# SensorBoard.net
KiCad netlist of a schematic drawn in Altium Designer
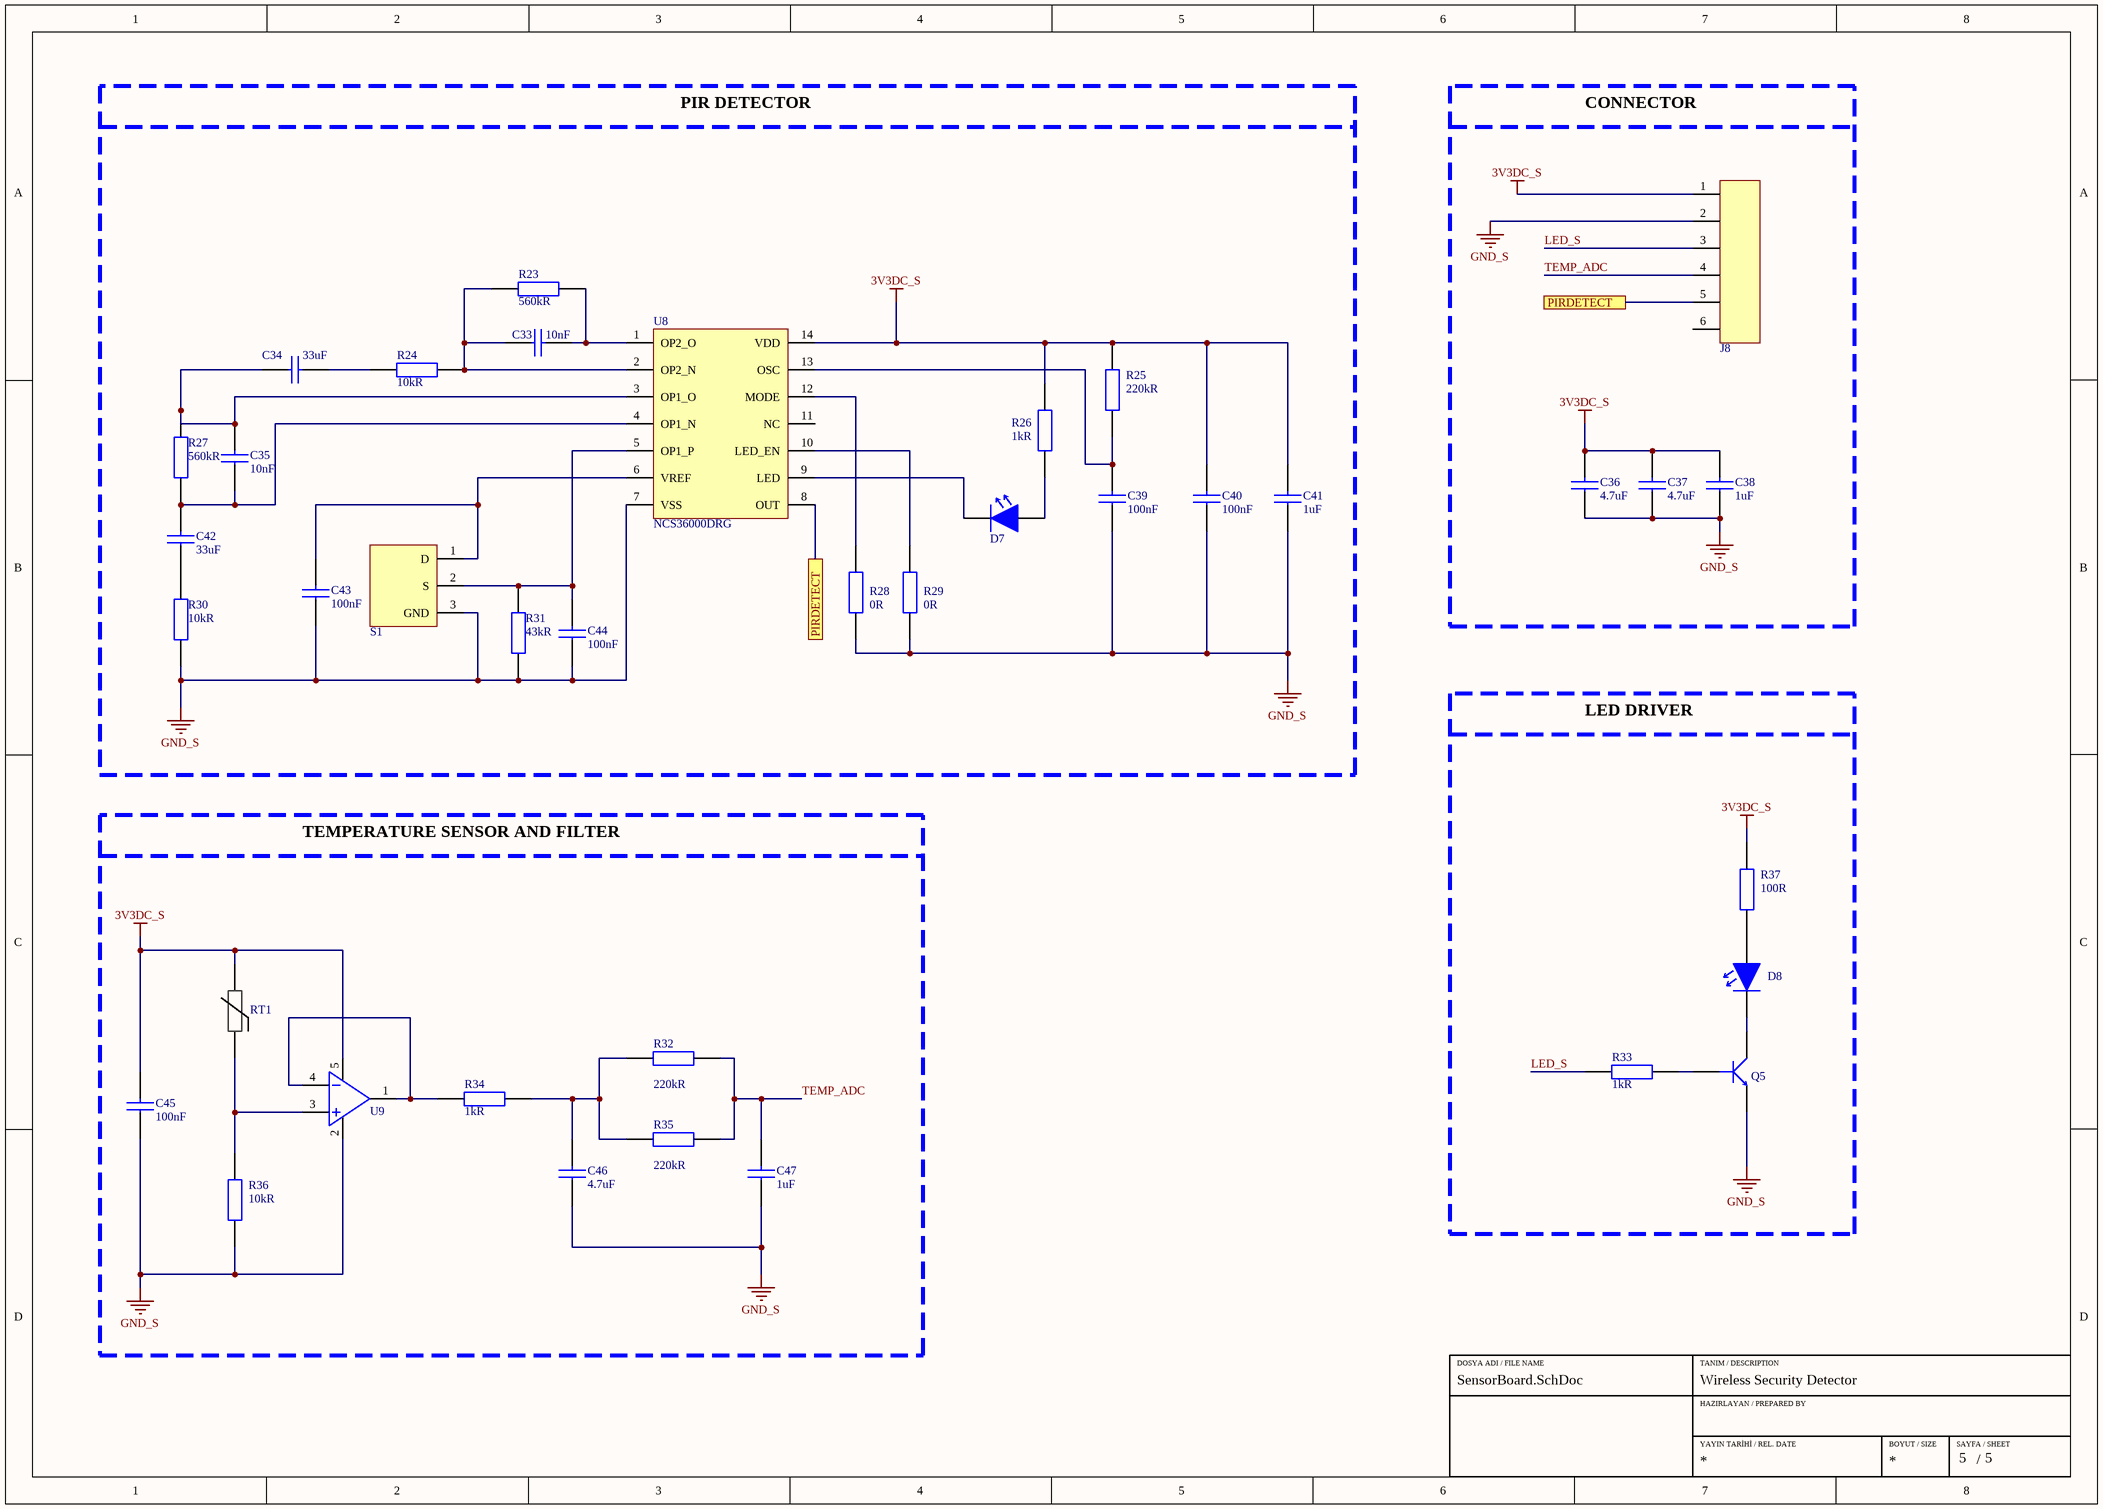
[diagram p0: SensorBoard.SchDoc]

(export (version "E")
  (design (tool "Eeschema 10.0.6"))
  (components
    (comp (ref "C33")
      (value "0603B103K160CT")
      (footprint "CAP_0603")
      (description "CAP CER 10nF %10 0603")
      (fields
        (field (name "MANUFACTURER") "Walsin Technologies")
        (field (name "TOLERANCE") "10%")
        (field (name "CAPACITANCE") "10nF")
        (field (name "DESIGNED BY") "BERK")
      )
      (libsource (lib "SECURITY_CAM") (part "CAP CER 10nF 0603"))
    )
    (comp (ref "C34")
      (value "C3216X5R1E336M160AC")
      (footprint "CAP_1206")
      (description "CAP CER 33uF %20 1206 SMD")
      (fields
        (field (name "MANUFACTURER") "TDK")
        (field (name "TOLERANCE") "20%")
        (field (name "CAPACITANCE") "33uF")
        (field (name "DESIGNED BY") "BERK")
      )
      (libsource (lib "SECURITY_CAM") (part "CAP CER 33uF 1206"))
    )
    (comp (ref "C35")
      (value "0603B103K160CT")
      (footprint "CAP_0603")
      (description "CAP CER 10nF %10 0603")
      (fields
        (field (name "MANUFACTURER") "Walsin Technologies")
        (field (name "TOLERANCE") "10%")
        (field (name "CAPACITANCE") "10nF")
        (field (name "DESIGNED BY") "BERK")
      )
      (libsource (lib "SECURITY_CAM") (part "CAP CER 10nF 0603"))
    )
    (comp (ref "C36")
      (value "CL21A475KAQNNNE")
      (footprint "CAP_0805")
      (description "CAP CER 4.7uF %10 0805")
      (fields
        (field (name "MANUFACTURER") "Samsung")
        (field (name "TOLERANCE") "10%")
        (field (name "CAPACITANCE") "4.7uF")
        (field (name "DESIGNED BY") "BERK")
      )
      (libsource (lib "SECURITY_CAM") (part "CAP CER 4.7uF 0805"))
    )
    (comp (ref "C37")
      (value "CL21A475KAQNNNE")
      (footprint "CAP_0805")
      (description "CAP CER 4.7uF %10 0805")
      (fields
        (field (name "MANUFACTURER") "Samsung")
        (field (name "TOLERANCE") "10%")
        (field (name "CAPACITANCE") "4.7uF")
        (field (name "DESIGNED BY") "BERK")
      )
      (libsource (lib "SECURITY_CAM") (part "CAP CER 4.7uF 0805"))
    )
    (comp (ref "C38")
      (value "CL21B105KBFNNNE")
      (footprint "CAP_0805")
      (description "CAP CER 1uF %10 0805")
      (fields
        (field (name "MANUFACTURER") "Samsung")
        (field (name "TOLERANCE") "10%")
        (field (name "CAPACITANCE") "1uF")
        (field (name "DESIGNED BY") "BERK")
      )
      (libsource (lib "SECURITY_CAM") (part "CAP CER 1uF 0805"))
    )
    (comp (ref "C39")
      (value "C0603C104K5RACTU")
      (footprint "CAP_0603")
      (description "CAP CER 100nF %10 0603 SMD")
      (fields
        (field (name "MANUFACTURER") "KEMET")
        (field (name "TOLERANCE") "10%")
        (field (name "CAPACITANCE") "100nF")
        (field (name "DESIGNED BY") "BERK")
      )
      (libsource (lib "SECURITY_CAM") (part "CAP CER 100nF 0603"))
    )
    (comp (ref "C40")
      (value "C0603C104K5RACTU")
      (footprint "CAP_0603")
      (description "CAP CER 100nF %10 0603 SMD")
      (fields
        (field (name "MANUFACTURER") "KEMET")
        (field (name "TOLERANCE") "10%")
        (field (name "CAPACITANCE") "100nF")
        (field (name "DESIGNED BY") "BERK")
      )
      (libsource (lib "SECURITY_CAM") (part "CAP CER 100nF 0603"))
    )
    (comp (ref "C41")
      (value "CL21B105KBFNNNE")
      (footprint "CAP_0805")
      (description "CAP CER 1uF %10 0805")
      (fields
        (field (name "MANUFACTURER") "Samsung")
        (field (name "TOLERANCE") "10%")
        (field (name "CAPACITANCE") "1uF")
        (field (name "DESIGNED BY") "BERK")
      )
      (libsource (lib "SECURITY_CAM") (part "CAP CER 1uF 0805"))
    )
    (comp (ref "C42")
      (value "C3216X5R1E336M160AC")
      (footprint "CAP_1206")
      (description "CAP CER 33uF %20 1206 SMD")
      (fields
        (field (name "MANUFACTURER") "TDK")
        (field (name "TOLERANCE") "20%")
        (field (name "CAPACITANCE") "33uF")
        (field (name "DESIGNED BY") "BERK")
      )
      (libsource (lib "SECURITY_CAM") (part "CAP CER 33uF 1206"))
    )
    (comp (ref "C43")
      (value "C0603C104K5RACTU")
      (footprint "CAP_0603")
      (description "CAP CER 100nF %10 0603 SMD")
      (fields
        (field (name "MANUFACTURER") "KEMET")
        (field (name "TOLERANCE") "10%")
        (field (name "CAPACITANCE") "100nF")
        (field (name "DESIGNED BY") "BERK")
      )
      (libsource (lib "SECURITY_CAM") (part "CAP CER 100nF 0603"))
    )
    (comp (ref "C44")
      (value "C0603C104K5RACTU")
      (footprint "CAP_0603")
      (description "CAP CER 100nF %10 0603 SMD")
      (fields
        (field (name "MANUFACTURER") "KEMET")
        (field (name "TOLERANCE") "10%")
        (field (name "CAPACITANCE") "100nF")
        (field (name "DESIGNED BY") "BERK")
      )
      (libsource (lib "SECURITY_CAM") (part "CAP CER 100nF 0603"))
    )
    (comp (ref "C45")
      (value "C0603C104K5RACTU")
      (footprint "CAP_0603")
      (description "CAP CER 100nF %10 0603 SMD")
      (fields
        (field (name "MANUFACTURER") "KEMET")
        (field (name "TOLERANCE") "10%")
        (field (name "CAPACITANCE") "100nF")
        (field (name "DESIGNED BY") "BERK")
      )
      (libsource (lib "SECURITY_CAM") (part "CAP CER 100nF 0603"))
    )
    (comp (ref "C46")
      (value "CL21A475KAQNNNE")
      (footprint "CAP_0805")
      (description "CAP CER 4.7uF %10 0805")
      (fields
        (field (name "MANUFACTURER") "Samsung")
        (field (name "TOLERANCE") "10%")
        (field (name "CAPACITANCE") "4.7uF")
        (field (name "DESIGNED BY") "BERK")
      )
      (libsource (lib "SECURITY_CAM") (part "CAP CER 4.7uF 0805"))
    )
    (comp (ref "C47")
      (value "CL21B105KBFNNNE")
      (footprint "CAP_0805")
      (description "CAP CER 1uF %10 0805")
      (fields
        (field (name "MANUFACTURER") "Samsung")
        (field (name "TOLERANCE") "10%")
        (field (name "CAPACITANCE") "1uF")
        (field (name "DESIGNED BY") "BERK")
      )
      (libsource (lib "SECURITY_CAM") (part "CAP CER 1uF 0805"))
    )
    (comp (ref "D7")
      (value "LTST-C171GKT")
      (footprint "LED_GREEN_0805")
      (description "Green 0805 130 º Min 5 mcd Typical 12 mcd Water Clear Lens SMT LED")
      (fields (field (name "MANUFACTURER") "Vishay Lite-On") (field (name "DESIGNED BY") "BERK"))
      (libsource (lib "SECURITY_CAM") (part "LED GREEN 0805"))
    )
    (comp (ref "D8")
      (value "LH R974-LP-1")
      (footprint "LED_RED_0805")
      (description "LED Uni-Color Hyper Red 660nm 2-Pin Chip 0805(2012Metric) T/R")
      (fields (field (name "MANUFACTURER") "Osram Opto") (field (name "DESIGNED BY") "BERK"))
      (libsource (lib "SECURITY_CAM") (part "LED RED 0805"))
    )
    (comp (ref "J8")
      (value "64800611622")
      (footprint "64800611622")
      (description "1.50mm 6PIN Connector")
      (fields (field (name "MANUFACTURER") "Wurth Electronics"))
      (libsource (lib "SECURITY_CAM") (part "64800611622_conn_6pin"))
    )
    (comp (ref "Q5")
      (value "MMBT3904-7-F")
      (footprint "SOT-23F")
      (description "Transistor General Purpose BJT NPN 40 Volt 0.2A Automotive 3-Pin SOT-23")
      (fields (field (name "MANUFACTURER") "Diodes Zetex") (field (name "DESIGNED BY") "BERK"))
      (libsource (lib "SECURITY_CAM") (part "MMBT3904-7-F"))
    )
    (comp (ref "R23")
      (value "RC0603JR-07560KL")
      (footprint "RES_0603")
      (description "RES SMD 560K OHM 5% 1/10W 0603")
      (fields
        (field (name "MANUFACTURER") "Yageo")
        (field (name "TOLERANCE") "5%")
        (field (name "RESISTANCE") "560kR")
        (field (name "DESIGNED BY") "BERK")
      )
      (libsource (lib "SECURITY_CAM") (part "RES 560K OHM 0603"))
    )
    (comp (ref "R24")
      (value "RC0603FR-0710KL")
      (footprint "RES_0603")
      (description "RES 10K %1 OHM 0603 SMD")
      (fields
        (field (name "MANUFACTURER") "Yageo")
        (field (name "TOLERANCE") "1%")
        (field (name "RESISTANCE") "10kR")
        (field (name "DESIGNED BY") "BERK")
      )
      (libsource (lib "") (part "RES 10K OHM 0603_1"))
    )
    (comp (ref "R25")
      (value "RC0603JR-07220KL")
      (footprint "RES_0603")
      (description "RES 220K %5 OHM 0603 SMD")
      (fields
        (field (name "MANUFACTURER") "Yageo")
        (field (name "TOLERANCE") "5%")
        (field (name "RESISTANCE") "220kR")
      )
      (libsource (lib "") (part "RES 220K OHM 0603_1"))
    )
    (comp (ref "R26")
      (value "RC0603FR-0710KL")
      (footprint "RES_0603")
      (description "RES 1K %1 OHM 0603 SMD")
      (fields
        (field (name "MANUFACTURER") "Yageo")
        (field (name "MANUFACTURER PART NUMBER") "RC0603JR-071KL")
        (field (name "RESISTANCE") "1kR")
        (field (name "DESIGNED BY") "BERK")
      )
      (libsource (lib "SECURITY_CAM") (part "RES 1K OHM 0603"))
    )
    (comp (ref "R27")
      (value "RC0603JR-07560KL")
      (footprint "RES_0603")
      (description "RES SMD 560K OHM 5% 1/10W 0603")
      (fields
        (field (name "MANUFACTURER") "Yageo")
        (field (name "TOLERANCE") "5%")
        (field (name "RESISTANCE") "560kR")
        (field (name "DESIGNED BY") "BERK")
      )
      (libsource (lib "") (part "RES 560K OHM 0603_1"))
    )
    (comp (ref "R28")
      (value "RC0603JR-070RL")
      (footprint "RES_0603")
      (description "RES 0 %1 OHM 0603 SMD")
      (fields
        (field (name "MANUFACTURER") "Yageo")
        (field (name "TOLERANCE") "1%")
        (field (name "RESISTANCE") "0R")
        (field (name "DESIGNED BY") "BERK")
      )
      (libsource (lib "SECURITY_CAM") (part "RES 0 OHM 0603"))
    )
    (comp (ref "R29")
      (value "RC0603JR-070RL")
      (footprint "RES_0603")
      (description "RES 0 %1 OHM 0603 SMD")
      (fields
        (field (name "MANUFACTURER") "Yageo")
        (field (name "TOLERANCE") "1%")
        (field (name "RESISTANCE") "0R")
        (field (name "DESIGNED BY") "BERK")
      )
      (libsource (lib "SECURITY_CAM") (part "RES 0 OHM 0603"))
    )
    (comp (ref "R30")
      (value "RC0603FR-0710KL")
      (footprint "RES_0603")
      (description "RES 10K %1 OHM 0603 SMD")
      (fields
        (field (name "MANUFACTURER") "Yageo")
        (field (name "TOLERANCE") "1%")
        (field (name "RESISTANCE") "10kR")
        (field (name "DESIGNED BY") "BERK")
      )
      (libsource (lib "SECURITY_CAM") (part "RES 10K OHM 0603"))
    )
    (comp (ref "R31")
      (value "RC0603JR-0743KL")
      (footprint "RES_0603")
      (description "RES 43K %5 OHM 0603 SMD")
      (fields
        (field (name "MANUFACTURER") "Yageo")
        (field (name "TOLERANCE") "5%")
        (field (name "RESISTANCE") "43kR")
        (field (name "DESIGNED BY") "BERK")
      )
      (libsource (lib "SECURITY_CAM") (part "RES 43K OHM 0603"))
    )
    (comp (ref "R32")
      (value "RC0603JR-07220KL")
      (footprint "RES_0603")
      (description "RES 220K %5 OHM 0603 SMD")
      (fields
        (field (name "MANUFACTURER") "Yageo")
        (field (name "TOLERANCE") "5%")
        (field (name "RESISTANCE") "220kR")
      )
      (libsource (lib "SECURITY_CAM") (part "RES 220K OHM 0603"))
    )
    (comp (ref "R33")
      (value "RC0603FR-0710KL")
      (footprint "RES_0603")
      (description "RES 1K %1 OHM 0603 SMD")
      (fields
        (field (name "MANUFACTURER") "Yageo")
        (field (name "MANUFACTURER PART NUMBER") "RC0603JR-071KL")
        (field (name "RESISTANCE") "1kR")
        (field (name "DESIGNED BY") "BERK")
      )
      (libsource (lib "") (part "RES 1K OHM 0603_2"))
    )
    (comp (ref "R34")
      (value "RC0603FR-0710KL")
      (footprint "RES_0603")
      (description "RES 1K %1 OHM 0603 SMD")
      (fields
        (field (name "MANUFACTURER") "Yageo")
        (field (name "MANUFACTURER PART NUMBER") "RC0603JR-071KL")
        (field (name "RESISTANCE") "1kR")
        (field (name "DESIGNED BY") "BERK")
      )
      (libsource (lib "") (part "RES 1K OHM 0603_1"))
    )
    (comp (ref "R35")
      (value "RC0603JR-07220KL")
      (footprint "RES_0603")
      (description "RES 220K %5 OHM 0603 SMD")
      (fields
        (field (name "MANUFACTURER") "Yageo")
        (field (name "TOLERANCE") "5%")
        (field (name "RESISTANCE") "220kR")
      )
      (libsource (lib "SECURITY_CAM") (part "RES 220K OHM 0603"))
    )
    (comp (ref "R36")
      (value "RC0603FR-0710KL")
      (footprint "RES_0603")
      (description "RES 10K %1 OHM 0603 SMD")
      (fields
        (field (name "MANUFACTURER") "Yageo")
        (field (name "TOLERANCE") "1%")
        (field (name "RESISTANCE") "10kR")
        (field (name "DESIGNED BY") "BERK")
      )
      (libsource (lib "SECURITY_CAM") (part "RES 10K OHM 0603"))
    )
    (comp (ref "R37")
      (value "RC0603JR-07100RL")
      (footprint "RES_0603")
      (description "RES 100 %5 OHM 0603 SMD")
      (fields
        (field (name "MANUFACTURER") "Yageo")
        (field (name "TOLERANCE") "5%")
        (field (name "RESISTANCE") "100R")
        (field (name "DESIGNED BY") "BERK")
      )
      (libsource (lib "SECURITY_CAM") (part "RES 100 OHM 0603"))
    )
    (comp (ref "RT1")
      (value "TFPT1206L1002FM")
      (footprint "RES_1206")
      (description "Thermistor PTC 10K Ohm 1% 1206")
      (fields
        (field (name "MANUFACTURER") "Vishay Dale")
        (field (name "TOLERANCE") "1%")
        (field (name "DESIGNED BY") "BERK")
      )
      (libsource (lib "SECURITY_CAM") (part "TFPT1206L1002FM"))
    )
    (comp (ref "S1")
      (value "LHI 878/3902")
      (footprint "LHI 878")
      (description "SENSOR PYRO DETECTOR DUAL MOTION")
      (fields (field (name "DESIGNED BY") "BERK"))
      (libsource (lib "SECURITY_CAM") (part "LHI 878/3902"))
    )
    (comp (ref "U8")
      (value "NCS36000DRG")
      (footprint "SOIC14")
      (description "PIR Controller Low Noise Amplifiers and LDO Regulator 14-Pin SOIC N T/R")
      (fields (field (name "MANUFACTURER") "ON Semiconductor") (field (name "DESIGNED BY") "BERK"))
      (libsource (lib "SECURITY_CAM") (part "NCS36000"))
    )
    (comp (ref "U9")
      (value "OPA314AIDBVR")
      (footprint "SOT23-5")
      (description "Op Amp OPA314")
      (fields (field (name "MANUFACTURER") "Texas Instruments") (field (name "DESIGNED BY") "BERK"))
      (libsource (lib "SECURITY_CAM") (part "OPA314"))
    )
  )
  (nets
    (net (code "1") (name "/LED_S") (class "Default")
      (node (ref "J8") (pin "3") (pintype "power_in"))
      (node (ref "R33") (pin "2") (pinfunction "2_2") (pintype "passive"))
    )
    (net (code "2") (name "/PIRDETECT") (class "Default")
      (node (ref "J8") (pin "5") (pintype "power_in"))
      (node (ref "U8") (pin "8") (pinfunction "OUT_8") (pintype "passive"))
    )
    (net (code "3") (name "/TEMP_ADC") (class "Default")
      (node (ref "C47") (pin "2") (pinfunction "2_2") (pintype "passive"))
      (node (ref "J8") (pin "4") (pintype "power_in"))
      (node (ref "R32") (pin "2") (pinfunction "2_2") (pintype "passive"))
      (node (ref "R35") (pin "2") (pinfunction "2_2") (pintype "passive"))
    )
    (net (code "4") (name "3V3DC_S") (class "Default")
      (node (ref "C36") (pin "2") (pinfunction "2_2") (pintype "passive"))
      (node (ref "C37") (pin "2") (pinfunction "2_2") (pintype "passive"))
      (node (ref "C38") (pin "2") (pinfunction "2_2") (pintype "passive"))
      (node (ref "C40") (pin "2") (pinfunction "2_2") (pintype "passive"))
      (node (ref "C41") (pin "2") (pinfunction "2_2") (pintype "passive"))
      (node (ref "C45") (pin "2") (pinfunction "2_2") (pintype "passive"))
      (node (ref "J8") (pin "1") (pintype "power_in"))
      (node (ref "R25") (pin "2") (pinfunction "2_2") (pintype "passive"))
      (node (ref "R26") (pin "2") (pinfunction "2_2") (pintype "passive"))
      (node (ref "R37") (pin "2") (pinfunction "2_2") (pintype "passive"))
      (node (ref "RT1") (pin "2") (pinfunction "2_2") (pintype "passive"))
      (node (ref "U8") (pin "14") (pinfunction "VDD_14") (pintype "passive"))
      (node (ref "U9") (pin "5") (pinfunction "5_5") (pintype "passive"))
    )
    (net (code "5") (name "GND_S") (class "Default")
      (node (ref "C36") (pin "1") (pinfunction "1_1") (pintype "passive"))
      (node (ref "C37") (pin "1") (pinfunction "1_1") (pintype "passive"))
      (node (ref "C38") (pin "1") (pinfunction "1_1") (pintype "passive"))
      (node (ref "C39") (pin "1") (pinfunction "1_1") (pintype "passive"))
      (node (ref "C40") (pin "1") (pinfunction "1_1") (pintype "passive"))
      (node (ref "C41") (pin "1") (pinfunction "1_1") (pintype "passive"))
      (node (ref "C43") (pin "1") (pinfunction "1_1") (pintype "passive"))
      (node (ref "C44") (pin "1") (pinfunction "1_1") (pintype "passive"))
      (node (ref "C45") (pin "1") (pinfunction "1_1") (pintype "passive"))
      (node (ref "C46") (pin "1") (pinfunction "1_1") (pintype "passive"))
      (node (ref "C47") (pin "1") (pinfunction "1_1") (pintype "passive"))
      (node (ref "J8") (pin "2") (pintype "power_in"))
      (node (ref "Q5") (pin "2") (pinfunction "E_2") (pintype "power_in"))
      (node (ref "R28") (pin "1") (pinfunction "1_1") (pintype "passive"))
      (node (ref "R29") (pin "1") (pinfunction "1_1") (pintype "passive"))
      (node (ref "R30") (pin "1") (pinfunction "1_1") (pintype "passive"))
      (node (ref "R31") (pin "1") (pinfunction "1_1") (pintype "passive"))
      (node (ref "R36") (pin "1") (pinfunction "1_1") (pintype "passive"))
      (node (ref "S1") (pin "3") (pinfunction "GND_3") (pintype "passive"))
      (node (ref "U8") (pin "7") (pinfunction "VSS_7") (pintype "passive"))
      (node (ref "U9") (pin "2") (pinfunction "2_2") (pintype "passive"))
    )
    (net (code "6") (name "Net-(C34-Pad2)") (class "Default")
      (node (ref "C34") (pin "2") (pinfunction "2_2") (pintype "passive"))
      (node (ref "R24") (pin "1") (pinfunction "1_1") (pintype "passive"))
    )
    (net (code "7") (name "Net-(C42-Pad1)") (class "Default")
      (node (ref "C42") (pin "1") (pinfunction "1_1") (pintype "passive"))
      (node (ref "R30") (pin "2") (pinfunction "2_2") (pintype "passive"))
    )
    (net (code "8") (name "Net-(C46-Pad2)") (class "Default")
      (node (ref "C46") (pin "2") (pinfunction "2_2") (pintype "passive"))
      (node (ref "R32") (pin "1") (pinfunction "1_1") (pintype "passive"))
      (node (ref "R34") (pin "2") (pinfunction "2_2") (pintype "passive"))
      (node (ref "R35") (pin "1") (pinfunction "1_1") (pintype "passive"))
    )
    (net (code "9") (name "Net-(D7-Pad2)") (class "Default")
      (node (ref "D7") (pin "2") (pinfunction "2_2") (pintype "power_in"))
      (node (ref "R26") (pin "1") (pinfunction "1_1") (pintype "passive"))
    )
    (net (code "10") (name "Net-(D8-Pad2)") (class "Default")
      (node (ref "D8") (pin "2") (pinfunction "2_2") (pintype "power_in"))
      (node (ref "R37") (pin "1") (pinfunction "1_1") (pintype "passive"))
    )
    (net (code "11") (name "Net-(Q5-B)") (class "Default")
      (node (ref "Q5") (pin "1") (pinfunction "B_1") (pintype "power_in"))
      (node (ref "R33") (pin "1") (pinfunction "1_1") (pintype "passive"))
    )
    (net (code "12") (name "Net-(Q5-C)") (class "Default")
      (node (ref "D8") (pin "1") (pinfunction "1_1") (pintype "power_in"))
      (node (ref "Q5") (pin "3") (pinfunction "C_3") (pintype "power_in"))
    )
    (net (code "13") (name "Net-(R34-Pad1)") (class "Default")
      (node (ref "R34") (pin "1") (pinfunction "1_1") (pintype "passive"))
      (node (ref "U9") (pin "1") (pinfunction "1_1") (pintype "passive"))
      (node (ref "U9") (pin "4") (pinfunction "4_4") (pintype "passive"))
    )
    (net (code "14") (name "Net-(R36-Pad2)") (class "Default")
      (node (ref "R36") (pin "2") (pinfunction "2_2") (pintype "passive"))
      (node (ref "RT1") (pin "1") (pinfunction "1_1") (pintype "passive"))
      (node (ref "U9") (pin "3") (pinfunction "3_3") (pintype "passive"))
    )
    (net (code "15") (name "Net-(S1-D)") (class "Default")
      (node (ref "C43") (pin "2") (pinfunction "2_2") (pintype "passive"))
      (node (ref "S1") (pin "1") (pinfunction "D_1") (pintype "passive"))
      (node (ref "U8") (pin "6") (pinfunction "VREF_6") (pintype "passive"))
    )
    (net (code "16") (name "Net-(S1-S)") (class "Default")
      (node (ref "C44") (pin "2") (pinfunction "2_2") (pintype "passive"))
      (node (ref "R31") (pin "2") (pinfunction "2_2") (pintype "passive"))
      (node (ref "S1") (pin "2") (pinfunction "S_2") (pintype "passive"))
      (node (ref "U8") (pin "5") (pinfunction "OP1_P_5") (pintype "passive"))
    )
    (net (code "17") (name "Net-(U8-LED)") (class "Default")
      (node (ref "D7") (pin "1") (pinfunction "1_1") (pintype "power_in"))
      (node (ref "U8") (pin "9") (pinfunction "LED_9") (pintype "passive"))
    )
    (net (code "18") (name "Net-(U8-LED_EN)") (class "Default")
      (node (ref "R29") (pin "2") (pinfunction "2_2") (pintype "passive"))
      (node (ref "U8") (pin "10") (pinfunction "LED_EN_10") (pintype "passive"))
    )
    (net (code "19") (name "Net-(U8-MODE)") (class "Default")
      (node (ref "R28") (pin "2") (pinfunction "2_2") (pintype "passive"))
      (node (ref "U8") (pin "12") (pinfunction "MODE_12") (pintype "passive"))
    )
    (net (code "20") (name "Net-(U8-OP1_N)") (class "Default")
      (node (ref "C35") (pin "1") (pinfunction "1_1") (pintype "passive"))
      (node (ref "C42") (pin "2") (pinfunction "2_2") (pintype "passive"))
      (node (ref "R27") (pin "1") (pinfunction "1_1") (pintype "passive"))
      (node (ref "U8") (pin "4") (pinfunction "OP1_N_4") (pintype "passive"))
    )
    (net (code "21") (name "Net-(U8-OP1_O)") (class "Default")
      (node (ref "C34") (pin "1") (pinfunction "1_1") (pintype "passive"))
      (node (ref "C35") (pin "2") (pinfunction "2_2") (pintype "passive"))
      (node (ref "R27") (pin "2") (pinfunction "2_2") (pintype "passive"))
      (node (ref "U8") (pin "3") (pinfunction "OP1_O_3") (pintype "passive"))
    )
    (net (code "22") (name "Net-(U8-OP2_N)") (class "Default")
      (node (ref "C33") (pin "1") (pinfunction "1_1") (pintype "passive"))
      (node (ref "R23") (pin "1") (pinfunction "1_1") (pintype "passive"))
      (node (ref "R24") (pin "2") (pinfunction "2_2") (pintype "passive"))
      (node (ref "U8") (pin "2") (pinfunction "OP2_N_2") (pintype "passive"))
    )
    (net (code "23") (name "Net-(U8-OP2_O)") (class "Default")
      (node (ref "C33") (pin "2") (pinfunction "2_2") (pintype "passive"))
      (node (ref "R23") (pin "2") (pinfunction "2_2") (pintype "passive"))
      (node (ref "U8") (pin "1") (pinfunction "OP2_O_1") (pintype "passive"))
    )
    (net (code "24") (name "Net-(U8-OSC)") (class "Default")
      (node (ref "C39") (pin "2") (pinfunction "2_2") (pintype "passive"))
      (node (ref "R25") (pin "1") (pinfunction "1_1") (pintype "passive"))
      (node (ref "U8") (pin "13") (pinfunction "OSC_13") (pintype "passive"))
    )
    (net (code "25") (name "unconnected-(J8-Pad6)") (class "Default")
      (node (ref "J8") (pin "6") (pintype "power_in"))
    )
    (net (code "26") (name "unconnected-(U8-NC-Pad11)") (class "Default")
      (node (ref "U8") (pin "11") (pinfunction "NC_11") (pintype "passive"))
    )
  )
)
